# FPGAPowerConfig.net
KiCad netlist of a schematic drawn in Altium Designer
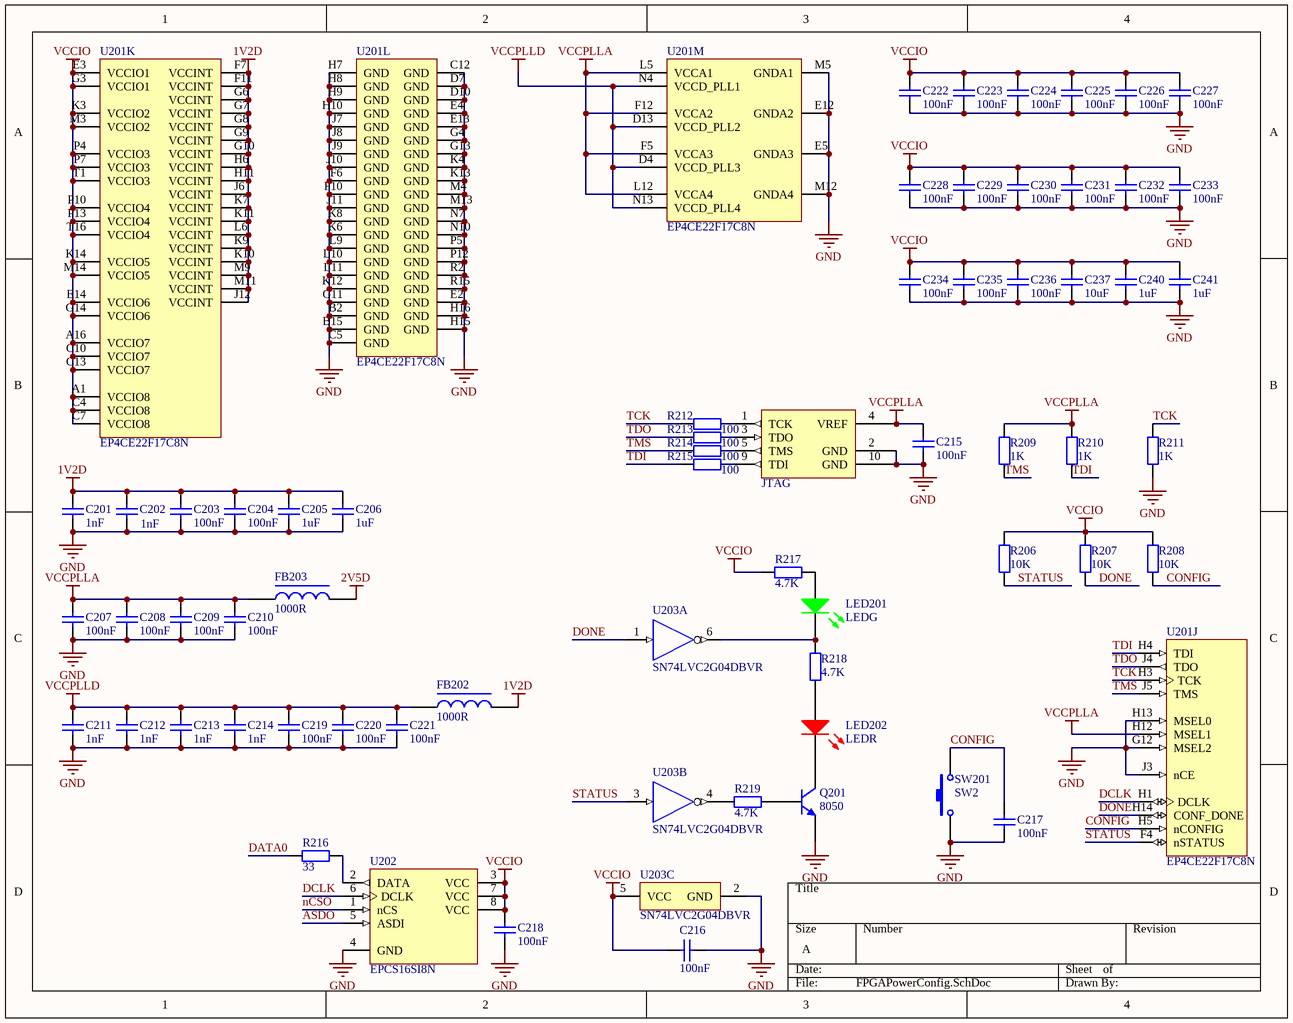
[diagram p0: FPGAPowerConfig.SchDoc]

(export (version "E")
  (design (tool "Eeschema 10.0.6"))
  (components
    (comp (ref "C201")
      (value "1nF")
      (footprint "0402C")
      (description "MLCC")
      (libsource (lib "Misc") (part "MLCC"))
    )
    (comp (ref "C202")
      (value "1nF")
      (footprint "0402C")
      (description "MLCC")
      (libsource (lib "Misc") (part "MLCC"))
    )
    (comp (ref "C203")
      (value "100nF")
      (footprint "0402C")
      (description "MLCC")
      (libsource (lib "Misc") (part "MLCC"))
    )
    (comp (ref "C204")
      (value "100nF")
      (footprint "0402C")
      (description "MLCC")
      (libsource (lib "Misc") (part "MLCC"))
    )
    (comp (ref "C205")
      (value "1uF")
      (footprint "0603C")
      (description "MLCC")
      (libsource (lib "Misc") (part "MLCC"))
    )
    (comp (ref "C206")
      (value "1uF")
      (footprint "0603C")
      (description "MLCC")
      (libsource (lib "Misc") (part "MLCC"))
    )
    (comp (ref "C207")
      (value "100nF")
      (footprint "0402C")
      (description "MLCC")
      (libsource (lib "Misc") (part "MLCC"))
    )
    (comp (ref "C208")
      (value "100nF")
      (footprint "0402C")
      (description "MLCC")
      (libsource (lib "Misc") (part "MLCC"))
    )
    (comp (ref "C209")
      (value "100nF")
      (footprint "0402C")
      (description "MLCC")
      (libsource (lib "Misc") (part "MLCC"))
    )
    (comp (ref "C210")
      (value "100nF")
      (footprint "0402C")
      (description "MLCC")
      (libsource (lib "Misc") (part "MLCC"))
    )
    (comp (ref "C211")
      (value "1nF")
      (footprint "0402C")
      (description "MLCC")
      (libsource (lib "Misc") (part "MLCC"))
    )
    (comp (ref "C212")
      (value "1nF")
      (footprint "0402C")
      (description "MLCC")
      (libsource (lib "Misc") (part "MLCC"))
    )
    (comp (ref "C213")
      (value "1nF")
      (footprint "0402C")
      (description "MLCC")
      (libsource (lib "Misc") (part "MLCC"))
    )
    (comp (ref "C214")
      (value "1nF")
      (footprint "0402C")
      (description "MLCC")
      (libsource (lib "Misc") (part "MLCC"))
    )
    (comp (ref "C215")
      (value "100nF")
      (footprint "0603C")
      (description "MLCC")
      (libsource (lib "Misc") (part "MLCC"))
    )
    (comp (ref "C216")
      (value "100nF")
      (footprint "0603C")
      (description "MLCC")
      (libsource (lib "Misc") (part "MLCC"))
    )
    (comp (ref "C217")
      (value "100nF")
      (footprint "0603C")
      (description "MLCC")
      (libsource (lib "Misc") (part "MLCC"))
    )
    (comp (ref "C218")
      (value "100nF")
      (footprint "0603C")
      (description "MLCC")
      (libsource (lib "Misc") (part "MLCC"))
    )
    (comp (ref "C219")
      (value "100nF")
      (footprint "0402C")
      (description "MLCC")
      (libsource (lib "Misc") (part "MLCC"))
    )
    (comp (ref "C220")
      (value "100nF")
      (footprint "0402C")
      (description "MLCC")
      (libsource (lib "Misc") (part "MLCC"))
    )
    (comp (ref "C221")
      (value "100nF")
      (footprint "0402C")
      (description "MLCC")
      (libsource (lib "Misc") (part "MLCC"))
    )
    (comp (ref "C222")
      (value "100nF")
      (footprint "0402C")
      (description "MLCC")
      (libsource (lib "Misc") (part "MLCC"))
    )
    (comp (ref "C223")
      (value "100nF")
      (footprint "0402C")
      (description "MLCC")
      (libsource (lib "Misc") (part "MLCC"))
    )
    (comp (ref "C224")
      (value "100nF")
      (footprint "0402C")
      (description "MLCC")
      (libsource (lib "Misc") (part "MLCC"))
    )
    (comp (ref "C225")
      (value "100nF")
      (footprint "0402C")
      (description "MLCC")
      (libsource (lib "Misc") (part "MLCC"))
    )
    (comp (ref "C226")
      (value "100nF")
      (footprint "0402C")
      (description "MLCC")
      (libsource (lib "Misc") (part "MLCC"))
    )
    (comp (ref "C227")
      (value "100nF")
      (footprint "0402C")
      (description "MLCC")
      (libsource (lib "Misc") (part "MLCC"))
    )
    (comp (ref "C228")
      (value "100nF")
      (footprint "0402C")
      (description "MLCC")
      (libsource (lib "Misc") (part "MLCC"))
    )
    (comp (ref "C229")
      (value "100nF")
      (footprint "0402C")
      (description "MLCC")
      (libsource (lib "Misc") (part "MLCC"))
    )
    (comp (ref "C230")
      (value "100nF")
      (footprint "0402C")
      (description "MLCC")
      (libsource (lib "Misc") (part "MLCC"))
    )
    (comp (ref "C231")
      (value "100nF")
      (footprint "0402C")
      (description "MLCC")
      (libsource (lib "Misc") (part "MLCC"))
    )
    (comp (ref "C232")
      (value "100nF")
      (footprint "0402C")
      (description "MLCC")
      (libsource (lib "Misc") (part "MLCC"))
    )
    (comp (ref "C233")
      (value "100nF")
      (footprint "0402C")
      (description "MLCC")
      (libsource (lib "Misc") (part "MLCC"))
    )
    (comp (ref "C234")
      (value "100nF")
      (footprint "0402C")
      (description "MLCC")
      (libsource (lib "Misc") (part "MLCC"))
    )
    (comp (ref "C235")
      (value "100nF")
      (footprint "0402C")
      (description "MLCC")
      (libsource (lib "Misc") (part "MLCC"))
    )
    (comp (ref "C236")
      (value "100nF")
      (footprint "0402C")
      (description "MLCC")
      (libsource (lib "Misc") (part "MLCC"))
    )
    (comp (ref "C237")
      (value "10uF")
      (footprint "0805C")
      (description "MLCC")
      (libsource (lib "Misc") (part "MLCC"))
    )
    (comp (ref "C240")
      (value "1uF")
      (footprint "0603C")
      (description "MLCC")
      (libsource (lib "Misc") (part "MLCC"))
    )
    (comp (ref "C241")
      (value "1uF")
      (footprint "0603C")
      (description "MLCC")
      (libsource (lib "Misc") (part "MLCC"))
    )
    (comp (ref "FB202")
      (value "1000R")
      (footprint "0603L")
      (description "FerriteBead")
      (libsource (lib "Misc") (part "FerriteBead"))
    )
    (comp (ref "FB203")
      (value "1000R")
      (footprint "0603L")
      (description "FerriteBead")
      (libsource (lib "Misc") (part "FerriteBead"))
    )
    (comp (ref "JTAG")
      (value "JTAG_ALTERA")
      (footprint "JTAG10")
      (description "ALTERA JTAG port")
      (libsource (lib "JTAG") (part "JTAG_ALTERA"))
    )
    (comp (ref "LED201")
      (value "LEDG")
      (footprint "LED1206G")
      (description "GREEN LED")
      (libsource (lib "Misc") (part "LEDG"))
    )
    (comp (ref "LED202")
      (value "LEDR")
      (footprint "LED1206R")
      (description "RED LED")
      (libsource (lib "Misc") (part "LEDR"))
    )
    (comp (ref "Q201")
      (value "8050")
      (footprint "SOT-23")
      (description "NPN Bipolar Transistor")
      (libsource (lib "Misc") (part "8050"))
    )
    (comp (ref "R206")
      (value "10K")
      (footprint "0603R")
      (description "Resistor")
      (libsource (lib "Misc") (part "Resistor"))
    )
    (comp (ref "R207")
      (value "10K")
      (footprint "0603R")
      (description "Resistor")
      (libsource (lib "Misc") (part "Resistor"))
    )
    (comp (ref "R208")
      (value "10K")
      (footprint "0603R")
      (description "Resistor")
      (libsource (lib "Misc") (part "Resistor"))
    )
    (comp (ref "R209")
      (value "1K")
      (footprint "0603R")
      (description "Resistor")
      (libsource (lib "Misc") (part "Resistor"))
    )
    (comp (ref "R210")
      (value "1K")
      (footprint "0603R")
      (description "Resistor")
      (libsource (lib "Misc") (part "Resistor"))
    )
    (comp (ref "R211")
      (value "1K")
      (footprint "0603R")
      (description "Resistor")
      (libsource (lib "Misc") (part "Resistor"))
    )
    (comp (ref "R212")
      (value "100")
      (footprint "0603R")
      (description "Resistor")
      (libsource (lib "") (part "Resistor_1"))
    )
    (comp (ref "R213")
      (value "100")
      (footprint "0603R")
      (description "Resistor")
      (libsource (lib "") (part "Resistor_1"))
    )
    (comp (ref "R214")
      (value "100")
      (footprint "0603R")
      (description "Resistor")
      (libsource (lib "") (part "Resistor_1"))
    )
    (comp (ref "R215")
      (value "100")
      (footprint "0603R")
      (description "Resistor")
      (libsource (lib "") (part "Resistor_1"))
    )
    (comp (ref "R216")
      (value "33")
      (footprint "0603R")
      (description "Resistor")
      (libsource (lib "") (part "Resistor_1"))
    )
    (comp (ref "R217")
      (value "4.7K")
      (footprint "0603R")
      (description "Resistor")
      (libsource (lib "") (part "Resistor_1"))
    )
    (comp (ref "R218")
      (value "4.7K")
      (footprint "0603R")
      (description "Resistor")
      (libsource (lib "Misc") (part "Resistor"))
    )
    (comp (ref "R219")
      (value "4.7K")
      (footprint "0603R")
      (description "Resistor")
      (libsource (lib "") (part "Resistor_1"))
    )
    (comp (ref "SW201")
      (value "SW2")
      (footprint "SW-SMD1")
      (description "Switch")
      (libsource (lib "Switch") (part "SW2"))
    )
    (comp (ref "U201")
      (value "EP4CE22F17C8N")
      (footprint "FBGA256_A-155")
      (fields (field (name "MANUFACTURER") "Altera"))
      (libsource (lib "Altera Cyclone IV E") (part "EP4CE22F17C8N"))
    )
    (comp (ref "U202")
      (value "EPCS16SI8N")
      (footprint "SOIC8_N")
      (libsource (lib "Altera EPCS") (part "EPCS16SI8N"))
    )
    (comp (ref "U203")
      (value "SN74LVC2G04DBVR")
      (footprint "DBV0006A_N")
      (description "Dual Inverter, DBV0006A, LARGE T&R")
      (fields
        (field (name "GENERIC PART NUMBER") "SN74LVC2G04")
        (field (name "MANUFACTURER") "Texas Instruments")
      )
      (libsource (lib "TI_Logic_Little_Logic") (part "SN74LVC2G04DBVR"))
    )
  )
  (nets
    (net (code "1") (name "/ASDO") (class "Default")
      (node (ref "U202") (pin "5") (pinfunction "ASDI_5") (pintype "input"))
    )
    (net (code "2") (name "/CONFIG") (class "Default")
      (node (ref "C217") (pin "2") (pinfunction "2_2") (pintype "passive"))
      (node (ref "R208") (pin "1") (pinfunction "1_1") (pintype "passive"))
      (node (ref "SW201") (pin "2") (pinfunction "2_2") (pintype "passive"))
      (node (ref "U201") (pin "H5") (pinfunction "nCONFIG_H5") (pintype "input"))
    )
    (net (code "3") (name "/DATA0") (class "Default")
      (node (ref "R216") (pin "1") (pinfunction "1_1") (pintype "passive"))
    )
    (net (code "4") (name "/DCLK") (class "Default")
      (node (ref "U201") (pin "H1") (pinfunction "DCLK_H1") (pintype "bidirectional"))
      (node (ref "U202") (pin "6") (pinfunction "DCLK_6") (pintype "input"))
    )
    (net (code "5") (name "/DONE") (class "Default")
      (node (ref "R207") (pin "1") (pinfunction "1_1") (pintype "passive"))
      (node (ref "U201") (pin "H14") (pinfunction "CONF_DONE_H14") (pintype "bidirectional"))
      (node (ref "U203") (pin "1") (pinfunction "1A_1") (pintype "input"))
    )
    (net (code "6") (name "/STATUS") (class "Default")
      (node (ref "R206") (pin "1") (pinfunction "1_1") (pintype "passive"))
      (node (ref "U201") (pin "F4") (pinfunction "nSTATUS_F4") (pintype "bidirectional"))
      (node (ref "U203") (pin "3") (pinfunction "2A_3") (pintype "input"))
    )
    (net (code "7") (name "/TCK") (class "Default")
      (node (ref "R211") (pin "2") (pinfunction "2_2") (pintype "passive"))
      (node (ref "R212") (pin "1") (pinfunction "1_1") (pintype "passive"))
      (node (ref "U201") (pin "H3") (pinfunction "TCK_H3") (pintype "input"))
    )
    (net (code "8") (name "/TDI") (class "Default")
      (node (ref "R210") (pin "1") (pinfunction "1_1") (pintype "passive"))
      (node (ref "R215") (pin "1") (pinfunction "1_1") (pintype "passive"))
      (node (ref "U201") (pin "H4") (pinfunction "TDI_H4") (pintype "input"))
    )
    (net (code "9") (name "/TDO") (class "Default")
      (node (ref "R213") (pin "1") (pinfunction "1_1") (pintype "passive"))
      (node (ref "U201") (pin "J4") (pinfunction "TDO_J4") (pintype "output"))
    )
    (net (code "10") (name "/TMS") (class "Default")
      (node (ref "R209") (pin "1") (pinfunction "1_1") (pintype "passive"))
      (node (ref "R214") (pin "1") (pinfunction "1_1") (pintype "passive"))
      (node (ref "U201") (pin "J5") (pinfunction "TMS_J5") (pintype "input"))
    )
    (net (code "11") (name "/nCSO") (class "Default")
      (node (ref "U202") (pin "1") (pinfunction "nCS_1") (pintype "input"))
    )
    (net (code "12") (name "1V2D") (class "Default")
      (node (ref "C201") (pin "2") (pinfunction "2_2") (pintype "passive"))
      (node (ref "C202") (pin "2") (pinfunction "2_2") (pintype "passive"))
      (node (ref "C203") (pin "2") (pinfunction "2_2") (pintype "passive"))
      (node (ref "C204") (pin "2") (pinfunction "2_2") (pintype "passive"))
      (node (ref "C205") (pin "2") (pinfunction "2_2") (pintype "passive"))
      (node (ref "C206") (pin "2") (pinfunction "2_2") (pintype "passive"))
      (node (ref "FB202") (pin "2") (pinfunction "2_2") (pintype "passive"))
      (node (ref "U201") (pin "F11") (pinfunction "VCCINT_F11") (pintype "power_in"))
      (node (ref "U201") (pin "F7") (pinfunction "VCCINT_F7") (pintype "power_in"))
      (node (ref "U201") (pin "G10") (pinfunction "VCCINT_G10") (pintype "power_in"))
      (node (ref "U201") (pin "G6") (pinfunction "VCCINT_G6") (pintype "power_in"))
      (node (ref "U201") (pin "G7") (pinfunction "VCCINT_G7") (pintype "power_in"))
      (node (ref "U201") (pin "G8") (pinfunction "VCCINT_G8") (pintype "power_in"))
      (node (ref "U201") (pin "G9") (pinfunction "VCCINT_G9") (pintype "power_in"))
      (node (ref "U201") (pin "H11") (pinfunction "VCCINT_H11") (pintype "power_in"))
      (node (ref "U201") (pin "H6") (pinfunction "VCCINT_H6") (pintype "power_in"))
      (node (ref "U201") (pin "J12") (pinfunction "VCCINT_J12") (pintype "power_in"))
      (node (ref "U201") (pin "J6") (pinfunction "VCCINT_J6") (pintype "power_in"))
      (node (ref "U201") (pin "K10") (pinfunction "VCCINT_K10") (pintype "power_in"))
      (node (ref "U201") (pin "K11") (pinfunction "VCCINT_K11") (pintype "power_in"))
      (node (ref "U201") (pin "K7") (pinfunction "VCCINT_K7") (pintype "power_in"))
      (node (ref "U201") (pin "K9") (pinfunction "VCCINT_K9") (pintype "power_in"))
      (node (ref "U201") (pin "L6") (pinfunction "VCCINT_L6") (pintype "power_in"))
      (node (ref "U201") (pin "M11") (pinfunction "VCCINT_M11") (pintype "power_in"))
      (node (ref "U201") (pin "M9") (pinfunction "VCCINT_M9") (pintype "power_in"))
    )
    (net (code "13") (name "2V5D") (class "Default")
      (node (ref "FB203") (pin "2") (pinfunction "2_2") (pintype "passive"))
    )
    (net (code "14") (name "GND") (class "Default")
      (node (ref "C201") (pin "1") (pinfunction "1_1") (pintype "passive"))
      (node (ref "C202") (pin "1") (pinfunction "1_1") (pintype "passive"))
      (node (ref "C203") (pin "1") (pinfunction "1_1") (pintype "passive"))
      (node (ref "C204") (pin "1") (pinfunction "1_1") (pintype "passive"))
      (node (ref "C205") (pin "1") (pinfunction "1_1") (pintype "passive"))
      (node (ref "C206") (pin "1") (pinfunction "1_1") (pintype "passive"))
      (node (ref "C207") (pin "1") (pinfunction "1_1") (pintype "passive"))
      (node (ref "C208") (pin "1") (pinfunction "1_1") (pintype "passive"))
      (node (ref "C209") (pin "1") (pinfunction "1_1") (pintype "passive"))
      (node (ref "C210") (pin "1") (pinfunction "1_1") (pintype "passive"))
      (node (ref "C211") (pin "1") (pinfunction "1_1") (pintype "passive"))
      (node (ref "C212") (pin "1") (pinfunction "1_1") (pintype "passive"))
      (node (ref "C213") (pin "1") (pinfunction "1_1") (pintype "passive"))
      (node (ref "C214") (pin "1") (pinfunction "1_1") (pintype "passive"))
      (node (ref "C215") (pin "1") (pinfunction "1_1") (pintype "passive"))
      (node (ref "C216") (pin "2") (pinfunction "2_2") (pintype "passive"))
      (node (ref "C217") (pin "1") (pinfunction "1_1") (pintype "passive"))
      (node (ref "C218") (pin "1") (pinfunction "1_1") (pintype "passive"))
      (node (ref "C219") (pin "1") (pinfunction "1_1") (pintype "passive"))
      (node (ref "C220") (pin "1") (pinfunction "1_1") (pintype "passive"))
      (node (ref "C221") (pin "1") (pinfunction "1_1") (pintype "passive"))
      (node (ref "C222") (pin "1") (pinfunction "1_1") (pintype "passive"))
      (node (ref "C223") (pin "1") (pinfunction "1_1") (pintype "passive"))
      (node (ref "C224") (pin "1") (pinfunction "1_1") (pintype "passive"))
      (node (ref "C225") (pin "1") (pinfunction "1_1") (pintype "passive"))
      (node (ref "C226") (pin "1") (pinfunction "1_1") (pintype "passive"))
      (node (ref "C227") (pin "1") (pinfunction "1_1") (pintype "passive"))
      (node (ref "C228") (pin "1") (pinfunction "1_1") (pintype "passive"))
      (node (ref "C229") (pin "1") (pinfunction "1_1") (pintype "passive"))
      (node (ref "C230") (pin "1") (pinfunction "1_1") (pintype "passive"))
      (node (ref "C231") (pin "1") (pinfunction "1_1") (pintype "passive"))
      (node (ref "C232") (pin "1") (pinfunction "1_1") (pintype "passive"))
      (node (ref "C233") (pin "1") (pinfunction "1_1") (pintype "passive"))
      (node (ref "C234") (pin "1") (pinfunction "1_1") (pintype "passive"))
      (node (ref "C235") (pin "1") (pinfunction "1_1") (pintype "passive"))
      (node (ref "C236") (pin "1") (pinfunction "1_1") (pintype "passive"))
      (node (ref "C237") (pin "1") (pinfunction "1_1") (pintype "passive"))
      (node (ref "C240") (pin "1") (pinfunction "1_1") (pintype "passive"))
      (node (ref "C241") (pin "1") (pinfunction "1_1") (pintype "passive"))
      (node (ref "JTAG") (pin "10") (pinfunction "GND_10") (pintype "power_in"))
      (node (ref "JTAG") (pin "2") (pinfunction "GND_2") (pintype "power_in"))
      (node (ref "Q201") (pin "2") (pinfunction "E_2") (pintype "passive"))
      (node (ref "R211") (pin "1") (pinfunction "1_1") (pintype "passive"))
      (node (ref "SW201") (pin "1") (pinfunction "1_1") (pintype "passive"))
      (node (ref "U201") (pin "B15") (pinfunction "GND_B15") (pintype "power_in"))
      (node (ref "U201") (pin "B2") (pinfunction "GND_B2") (pintype "power_in"))
      (node (ref "U201") (pin "C12") (pinfunction "GND_C12") (pintype "power_in"))
      (node (ref "U201") (pin "C5") (pinfunction "GND_C5") (pintype "power_in"))
      (node (ref "U201") (pin "D10") (pinfunction "GND_D10") (pintype "power_in"))
      (node (ref "U201") (pin "D7") (pinfunction "GND_D7") (pintype "power_in"))
      (node (ref "U201") (pin "E12") (pinfunction "GNDA2_E12") (pintype "power_in"))
      (node (ref "U201") (pin "E13") (pinfunction "GND_E13") (pintype "power_in"))
      (node (ref "U201") (pin "E2") (pinfunction "GND_E2") (pintype "power_in"))
      (node (ref "U201") (pin "E4") (pinfunction "GND_E4") (pintype "power_in"))
      (node (ref "U201") (pin "E5") (pinfunction "GNDA3_E5") (pintype "power_in"))
      (node (ref "U201") (pin "F10") (pinfunction "GND_F10") (pintype "power_in"))
      (node (ref "U201") (pin "F6") (pinfunction "GND_F6") (pintype "power_in"))
      (node (ref "U201") (pin "G11") (pinfunction "GND_G11") (pintype "power_in"))
      (node (ref "U201") (pin "G12") (pinfunction "MSEL2_G12") (pintype "input"))
      (node (ref "U201") (pin "G13") (pinfunction "GND_G13") (pintype "power_in"))
      (node (ref "U201") (pin "G4") (pinfunction "GND_G4") (pintype "power_in"))
      (node (ref "U201") (pin "H10") (pinfunction "GND_H10") (pintype "power_in"))
      (node (ref "U201") (pin "H13") (pinfunction "MSEL0_H13") (pintype "input"))
      (node (ref "U201") (pin "H15") (pinfunction "GND_H15") (pintype "power_in"))
      (node (ref "U201") (pin "H16") (pinfunction "GND_H16") (pintype "power_in"))
      (node (ref "U201") (pin "H7") (pinfunction "GND_H7") (pintype "power_in"))
      (node (ref "U201") (pin "H8") (pinfunction "GND_H8") (pintype "power_in"))
      (node (ref "U201") (pin "H9") (pinfunction "GND_H9") (pintype "power_in"))
      (node (ref "U201") (pin "J10") (pinfunction "GND_J10") (pintype "power_in"))
      (node (ref "U201") (pin "J11") (pinfunction "GND_J11") (pintype "power_in"))
      (node (ref "U201") (pin "J3") (pinfunction "nCE_J3") (pintype "input"))
      (node (ref "U201") (pin "J7") (pinfunction "GND_J7") (pintype "power_in"))
      (node (ref "U201") (pin "J8") (pinfunction "GND_J8") (pintype "power_in"))
      (node (ref "U201") (pin "J9") (pinfunction "GND_J9") (pintype "power_in"))
      (node (ref "U201") (pin "K12") (pinfunction "GND_K12") (pintype "power_in"))
      (node (ref "U201") (pin "K13") (pinfunction "GND_K13") (pintype "power_in"))
      (node (ref "U201") (pin "K4") (pinfunction "GND_K4") (pintype "power_in"))
      (node (ref "U201") (pin "K6") (pinfunction "GND_K6") (pintype "power_in"))
      (node (ref "U201") (pin "K8") (pinfunction "GND_K8") (pintype "power_in"))
      (node (ref "U201") (pin "L10") (pinfunction "GND_L10") (pintype "power_in"))
      (node (ref "U201") (pin "L11") (pinfunction "GND_L11") (pintype "power_in"))
      (node (ref "U201") (pin "L9") (pinfunction "GND_L9") (pintype "power_in"))
      (node (ref "U201") (pin "M12") (pinfunction "GNDA4_M12") (pintype "power_in"))
      (node (ref "U201") (pin "M13") (pinfunction "GND_M13") (pintype "power_in"))
      (node (ref "U201") (pin "M4") (pinfunction "GND_M4") (pintype "power_in"))
      (node (ref "U201") (pin "M5") (pinfunction "GNDA1_M5") (pintype "power_in"))
      (node (ref "U201") (pin "N10") (pinfunction "GND_N10") (pintype "power_in"))
      (node (ref "U201") (pin "N7") (pinfunction "GND_N7") (pintype "power_in"))
      (node (ref "U201") (pin "P12") (pinfunction "GND_P12") (pintype "power_in"))
      (node (ref "U201") (pin "P5") (pinfunction "GND_P5") (pintype "power_in"))
      (node (ref "U201") (pin "R15") (pinfunction "GND_R15") (pintype "power_in"))
      (node (ref "U201") (pin "R2") (pinfunction "GND_R2") (pintype "power_in"))
      (node (ref "U202") (pin "4") (pinfunction "GND_4") (pintype "power_in"))
      (node (ref "U203") (pin "2") (pinfunction "GND_2") (pintype "power_in"))
    )
    (net (code "15") (name "Net-(JTAG-TCK)") (class "Default")
      (node (ref "JTAG") (pin "1") (pinfunction "TCK_1") (pintype "output"))
      (node (ref "R212") (pin "2") (pinfunction "2_2") (pintype "passive"))
    )
    (net (code "16") (name "Net-(JTAG-TDI)") (class "Default")
      (node (ref "JTAG") (pin "9") (pinfunction "TDI_9") (pintype "output"))
      (node (ref "R215") (pin "2") (pinfunction "2_2") (pintype "passive"))
    )
    (net (code "17") (name "Net-(JTAG-TDO)") (class "Default")
      (node (ref "JTAG") (pin "3") (pinfunction "TDO_3") (pintype "input"))
      (node (ref "R213") (pin "2") (pinfunction "2_2") (pintype "passive"))
    )
    (net (code "18") (name "Net-(JTAG-TMS)") (class "Default")
      (node (ref "JTAG") (pin "5") (pinfunction "TMS_5") (pintype "output"))
      (node (ref "R214") (pin "2") (pinfunction "2_2") (pintype "passive"))
    )
    (net (code "19") (name "Net-(LED201-A)") (class "Default")
      (node (ref "LED201") (pin "1") (pinfunction "A_1") (pintype "passive"))
      (node (ref "R217") (pin "2") (pinfunction "2_2") (pintype "passive"))
    )
    (net (code "20") (name "Net-(LED201-K)") (class "Default")
      (node (ref "LED201") (pin "2") (pinfunction "K_2") (pintype "passive"))
      (node (ref "R218") (pin "2") (pinfunction "2_2") (pintype "passive"))
      (node (ref "U203") (pin "6") (pinfunction "1Y_6") (pintype "output"))
    )
    (net (code "21") (name "Net-(LED202-A)") (class "Default")
      (node (ref "LED202") (pin "1") (pinfunction "A_1") (pintype "passive"))
      (node (ref "R218") (pin "1") (pinfunction "1_1") (pintype "passive"))
    )
    (net (code "22") (name "Net-(LED202-K)") (class "Default")
      (node (ref "LED202") (pin "2") (pinfunction "K_2") (pintype "passive"))
      (node (ref "Q201") (pin "3") (pinfunction "C_3") (pintype "passive"))
    )
    (net (code "23") (name "Net-(Q201-B)") (class "Default")
      (node (ref "Q201") (pin "1") (pinfunction "B_1") (pintype "passive"))
      (node (ref "R219") (pin "2") (pinfunction "2_2") (pintype "passive"))
    )
    (net (code "24") (name "Net-(U202-DATA)") (class "Default")
      (node (ref "R216") (pin "2") (pinfunction "2_2") (pintype "passive"))
      (node (ref "U202") (pin "2") (pinfunction "DATA_2") (pintype "output"))
    )
    (net (code "25") (name "Net-(U203B-2Y)") (class "Default")
      (node (ref "R219") (pin "1") (pinfunction "1_1") (pintype "passive"))
      (node (ref "U203") (pin "4") (pinfunction "2Y_4") (pintype "output"))
    )
    (net (code "26") (name "VCCIO") (class "Default")
      (node (ref "C216") (pin "1") (pinfunction "1_1") (pintype "passive"))
      (node (ref "C218") (pin "2") (pinfunction "2_2") (pintype "passive"))
      (node (ref "C222") (pin "2") (pinfunction "2_2") (pintype "passive"))
      (node (ref "C223") (pin "2") (pinfunction "2_2") (pintype "passive"))
      (node (ref "C224") (pin "2") (pinfunction "2_2") (pintype "passive"))
      (node (ref "C225") (pin "2") (pinfunction "2_2") (pintype "passive"))
      (node (ref "C226") (pin "2") (pinfunction "2_2") (pintype "passive"))
      (node (ref "C227") (pin "2") (pinfunction "2_2") (pintype "passive"))
      (node (ref "C228") (pin "2") (pinfunction "2_2") (pintype "passive"))
      (node (ref "C229") (pin "2") (pinfunction "2_2") (pintype "passive"))
      (node (ref "C230") (pin "2") (pinfunction "2_2") (pintype "passive"))
      (node (ref "C231") (pin "2") (pinfunction "2_2") (pintype "passive"))
      (node (ref "C232") (pin "2") (pinfunction "2_2") (pintype "passive"))
      (node (ref "C233") (pin "2") (pinfunction "2_2") (pintype "passive"))
      (node (ref "C234") (pin "2") (pinfunction "2_2") (pintype "passive"))
      (node (ref "C235") (pin "2") (pinfunction "2_2") (pintype "passive"))
      (node (ref "C236") (pin "2") (pinfunction "2_2") (pintype "passive"))
      (node (ref "C237") (pin "2") (pinfunction "2_2") (pintype "passive"))
      (node (ref "C240") (pin "2") (pinfunction "2_2") (pintype "passive"))
      (node (ref "C241") (pin "2") (pinfunction "2_2") (pintype "passive"))
      (node (ref "R206") (pin "2") (pinfunction "2_2") (pintype "passive"))
      (node (ref "R207") (pin "2") (pinfunction "2_2") (pintype "passive"))
      (node (ref "R208") (pin "2") (pinfunction "2_2") (pintype "passive"))
      (node (ref "R217") (pin "1") (pinfunction "1_1") (pintype "passive"))
      (node (ref "U201") (pin "A1") (pinfunction "VCCIO8_A1") (pintype "power_in"))
      (node (ref "U201") (pin "A16") (pinfunction "VCCIO7_A16") (pintype "power_in"))
      (node (ref "U201") (pin "C10") (pinfunction "VCCIO7_C10") (pintype "power_in"))
      (node (ref "U201") (pin "C13") (pinfunction "VCCIO7_C13") (pintype "power_in"))
      (node (ref "U201") (pin "C4") (pinfunction "VCCIO8_C4") (pintype "power_in"))
      (node (ref "U201") (pin "C7") (pinfunction "VCCIO8_C7") (pintype "power_in"))
      (node (ref "U201") (pin "E14") (pinfunction "VCCIO6_E14") (pintype "power_in"))
      (node (ref "U201") (pin "E3") (pinfunction "VCCIO1_E3") (pintype "power_in"))
      (node (ref "U201") (pin "G14") (pinfunction "VCCIO6_G14") (pintype "power_in"))
      (node (ref "U201") (pin "G3") (pinfunction "VCCIO1_G3") (pintype "power_in"))
      (node (ref "U201") (pin "K14") (pinfunction "VCCIO5_K14") (pintype "power_in"))
      (node (ref "U201") (pin "K3") (pinfunction "VCCIO2_K3") (pintype "power_in"))
      (node (ref "U201") (pin "M14") (pinfunction "VCCIO5_M14") (pintype "power_in"))
      (node (ref "U201") (pin "M3") (pinfunction "VCCIO2_M3") (pintype "power_in"))
      (node (ref "U201") (pin "P10") (pinfunction "VCCIO4_P10") (pintype "power_in"))
      (node (ref "U201") (pin "P13") (pinfunction "VCCIO4_P13") (pintype "power_in"))
      (node (ref "U201") (pin "P4") (pinfunction "VCCIO3_P4") (pintype "power_in"))
      (node (ref "U201") (pin "P7") (pinfunction "VCCIO3_P7") (pintype "power_in"))
      (node (ref "U201") (pin "T1") (pinfunction "VCCIO3_T1") (pintype "power_in"))
      (node (ref "U201") (pin "T16") (pinfunction "VCCIO4_T16") (pintype "power_in"))
      (node (ref "U202") (pin "3") (pinfunction "VCC_3") (pintype "power_in"))
      (node (ref "U202") (pin "7") (pinfunction "VCC_7") (pintype "power_in"))
      (node (ref "U202") (pin "8") (pinfunction "VCC_8") (pintype "power_in"))
      (node (ref "U203") (pin "5") (pinfunction "VCC_5") (pintype "power_in"))
    )
    (net (code "27") (name "VCCPLLA") (class "Default")
      (node (ref "C207") (pin "2") (pinfunction "2_2") (pintype "passive"))
      (node (ref "C208") (pin "2") (pinfunction "2_2") (pintype "passive"))
      (node (ref "C209") (pin "2") (pinfunction "2_2") (pintype "passive"))
      (node (ref "C210") (pin "2") (pinfunction "2_2") (pintype "passive"))
      (node (ref "C215") (pin "2") (pinfunction "2_2") (pintype "passive"))
      (node (ref "FB203") (pin "1") (pinfunction "1_1") (pintype "passive"))
      (node (ref "JTAG") (pin "4") (pinfunction "VREF_4") (pintype "power_in"))
      (node (ref "R209") (pin "2") (pinfunction "2_2") (pintype "passive"))
      (node (ref "R210") (pin "2") (pinfunction "2_2") (pintype "passive"))
      (node (ref "U201") (pin "F12") (pinfunction "VCCA2_F12") (pintype "power_in"))
      (node (ref "U201") (pin "F5") (pinfunction "VCCA3_F5") (pintype "power_in"))
      (node (ref "U201") (pin "H12") (pinfunction "MSEL1_H12") (pintype "input"))
      (node (ref "U201") (pin "L12") (pinfunction "VCCA4_L12") (pintype "power_in"))
      (node (ref "U201") (pin "L5") (pinfunction "VCCA1_L5") (pintype "power_in"))
    )
    (net (code "28") (name "VCCPLLD") (class "Default")
      (node (ref "C211") (pin "2") (pinfunction "2_2") (pintype "passive"))
      (node (ref "C212") (pin "2") (pinfunction "2_2") (pintype "passive"))
      (node (ref "C213") (pin "2") (pinfunction "2_2") (pintype "passive"))
      (node (ref "C214") (pin "2") (pinfunction "2_2") (pintype "passive"))
      (node (ref "C219") (pin "2") (pinfunction "2_2") (pintype "passive"))
      (node (ref "C220") (pin "2") (pinfunction "2_2") (pintype "passive"))
      (node (ref "C221") (pin "2") (pinfunction "2_2") (pintype "passive"))
      (node (ref "FB202") (pin "1") (pinfunction "1_1") (pintype "passive"))
      (node (ref "U201") (pin "D13") (pinfunction "VCCD_PLL2_D13") (pintype "power_in"))
      (node (ref "U201") (pin "D4") (pinfunction "VCCD_PLL3_D4") (pintype "power_in"))
      (node (ref "U201") (pin "N13") (pinfunction "VCCD_PLL4_N13") (pintype "power_in"))
      (node (ref "U201") (pin "N4") (pinfunction "VCCD_PLL1_N4") (pintype "power_in"))
    )
  )
)
